# open-book.net
KiCad netlist of a schematic drawn in EAGLE
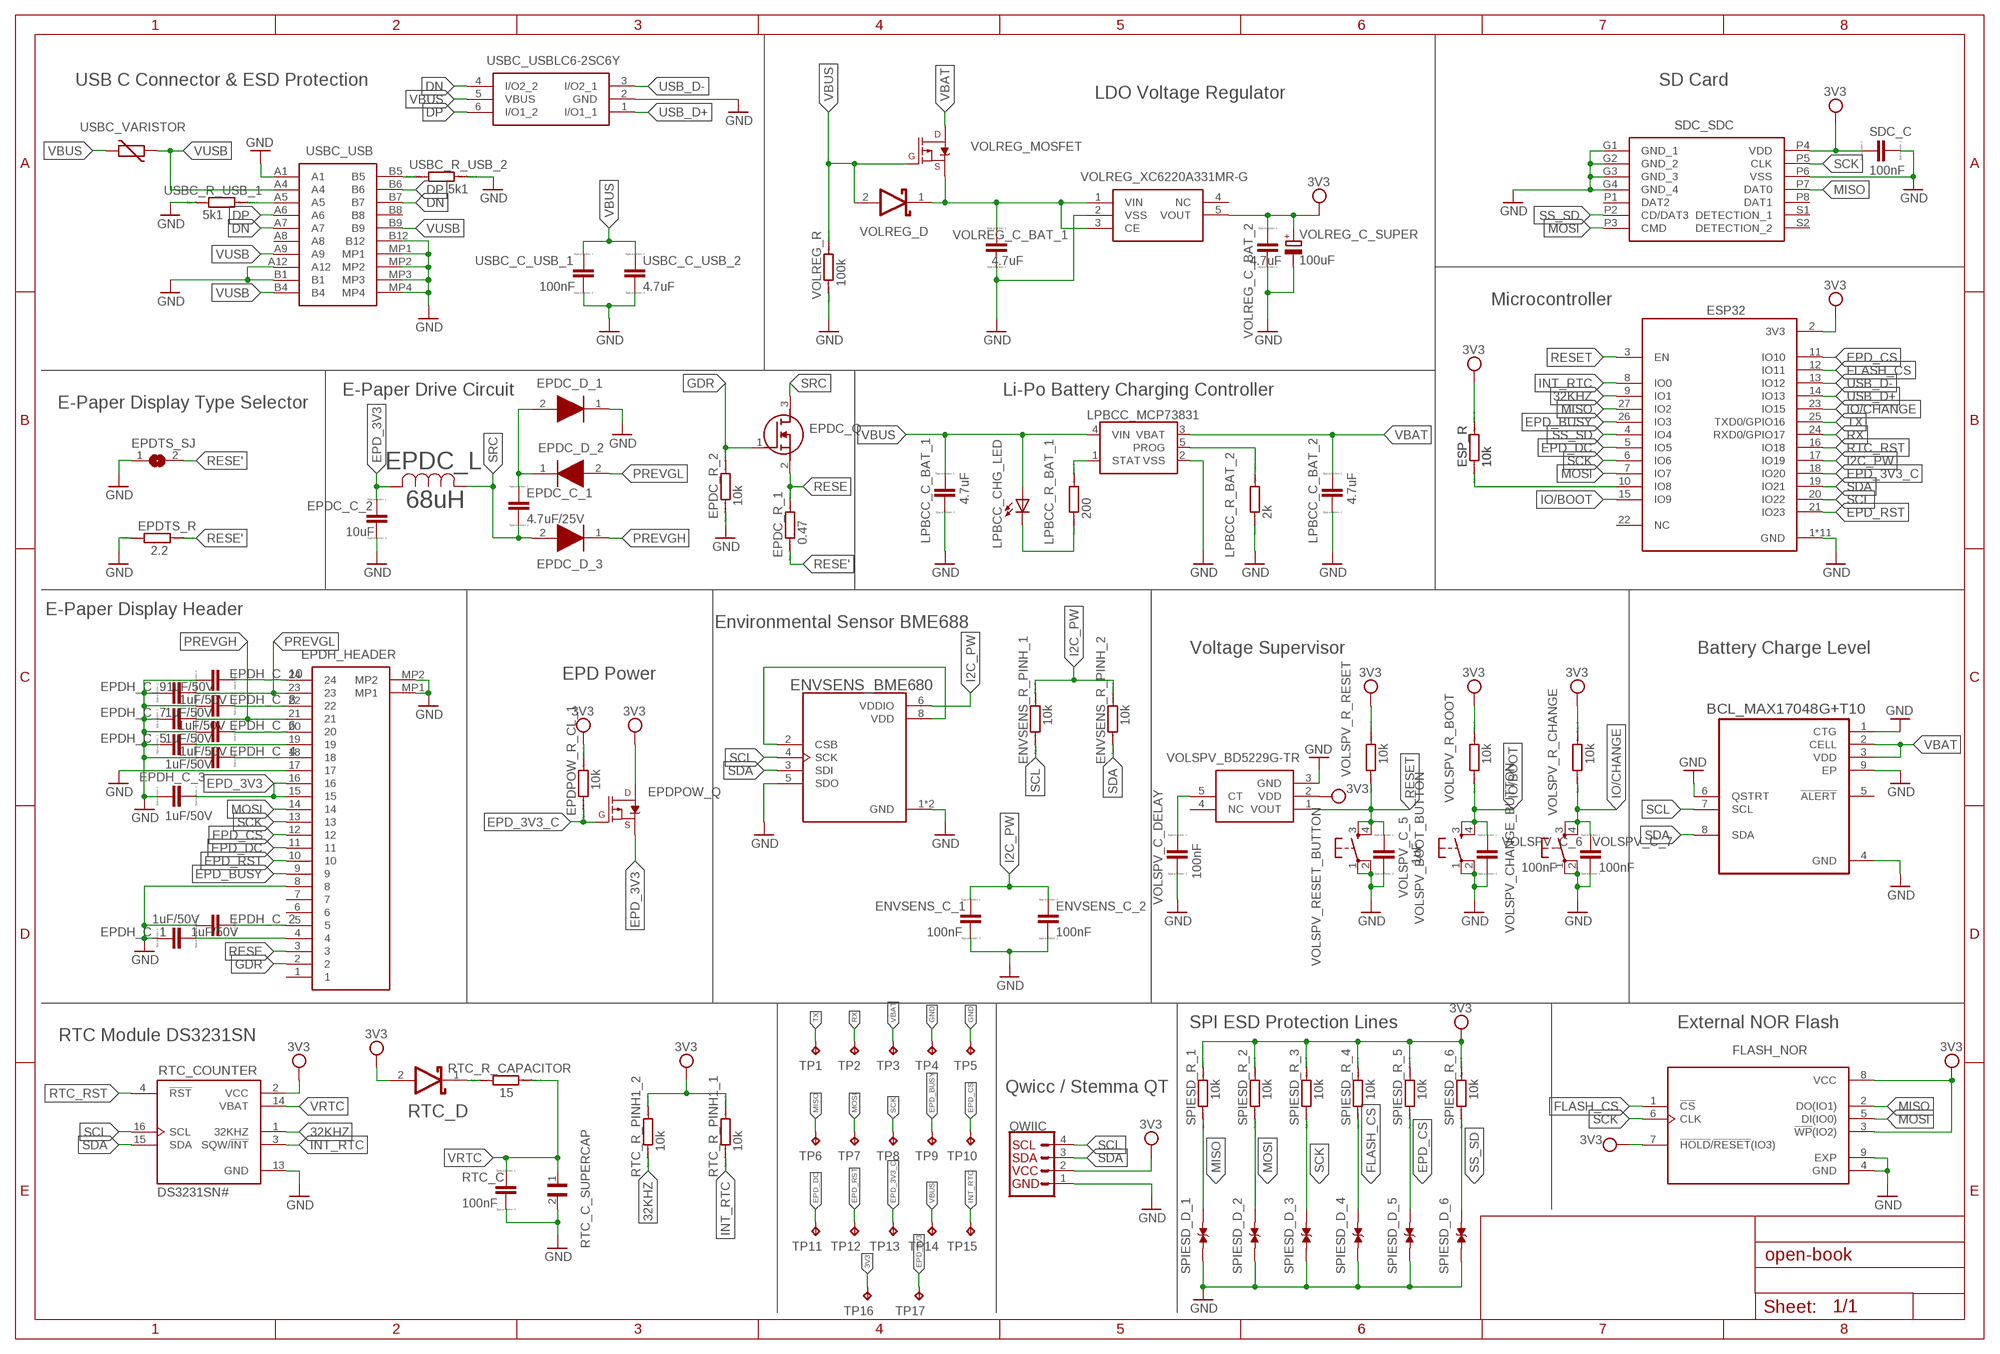
[diagram p0: schematic, sheet 1]

(export (version "E")
  (design (tool "Eeschema 10.0.6"))
  (components
    (comp (ref "BCL_MAX17048G+T10")
      (value "MAX17048G+T10")
      (footprint "eagle-import:SON50P200X200X80-9N")
      (libsource (lib "eagle-import") (part "MAX17048G+T10"))
    )
    (comp (ref "ENVSENS_BME680")
      (value "ESP32_WROVER_BME680_BME680")
      (footprint "eagle-import:ESP32_WROVER_BME680_PSON80P300X300X100-8N")
      (libsource (lib "eagle-import") (part "ESP32_WROVER_BME680_BME680"))
    )
    (comp (ref "ENVSENS_C_1")
      (value "100nF")
      (footprint "eagle-import:EAGLE-LTSPICE_C0402")
      (libsource (lib "eagle-import") (part "EAGLE-LTSPICE_CC0402"))
    )
    (comp (ref "ENVSENS_C_2")
      (value "100nF")
      (footprint "eagle-import:EAGLE-LTSPICE_C0402")
      (libsource (lib "eagle-import") (part "EAGLE-LTSPICE_CC0402"))
    )
    (comp (ref "ENVSENS_R_PINH_1")
      (value "10k")
      (footprint "eagle-import:ESP32_WROVER_EAGLE-LTSPICE_R0402")
      (libsource (lib "eagle-import") (part "ESP32_WROVER_EAGLE-LTSPICE_RR0402"))
    )
    (comp (ref "ENVSENS_R_PINH_2")
      (value "10k")
      (footprint "eagle-import:ESP32_WROVER_EAGLE-LTSPICE_R0402")
      (libsource (lib "eagle-import") (part "ESP32_WROVER_EAGLE-LTSPICE_RR0402"))
    )
    (comp (ref "EPDC_C_1")
      (value "4.7uF/25V")
      (footprint "eagle-import:EAGLE-LTSPICE_C0402")
      (libsource (lib "eagle-import") (part "EAGLE-LTSPICE_CC0402"))
    )
    (comp (ref "EPDC_C_2")
      (value "10uF")
      (footprint "eagle-import:EAGLE-LTSPICE_C0402")
      (libsource (lib "eagle-import") (part "EAGLE-LTSPICE_CC0402"))
    )
    (comp (ref "EPDC_D_1")
      (value "MBR0530")
      (footprint "eagle-import:SOD3716X135N")
      (libsource (lib "eagle-import") (part "MBR0530"))
    )
    (comp (ref "EPDC_D_2")
      (value "MBR0530")
      (footprint "eagle-import:SOD3716X135N")
      (libsource (lib "eagle-import") (part "MBR0530"))
    )
    (comp (ref "EPDC_D_3")
      (value "MBR0530")
      (footprint "eagle-import:SOD3716X135N")
      (libsource (lib "eagle-import") (part "MBR0530"))
    )
    (comp (ref "EPDC_L")
      (value "68uH")
      (footprint "eagle-import:IND_4828-WE-TPC_WRE")
      (libsource (lib "eagle-import") (part "744043680IND_4828-WE-TPC_WRE"))
    )
    (comp (ref "EPDC_Q")
      (value "SI1308EDL-T1-GE3")
      (footprint "eagle-import:SOT65P210X110-3N")
      (libsource (lib "eagle-import") (part "SI1308EDL-T1-GE3"))
    )
    (comp (ref "EPDC_R_1")
      (value "0.47")
      (footprint "eagle-import:ESP32_WROVER_EAGLE-LTSPICE_R0402")
      (libsource (lib "eagle-import") (part "ESP32_WROVER_EAGLE-LTSPICE_RR0402"))
    )
    (comp (ref "EPDC_R_2")
      (value "10k")
      (footprint "eagle-import:ESP32_WROVER_EAGLE-LTSPICE_R0402")
      (libsource (lib "eagle-import") (part "ESP32_WROVER_EAGLE-LTSPICE_RR0402"))
    )
    (comp (ref "EPDH_C_1")
      (value "1uF/50V")
      (footprint "eagle-import:EAGLE-LTSPICE_C0402")
      (libsource (lib "eagle-import") (part "EAGLE-LTSPICE_CC0402"))
    )
    (comp (ref "EPDH_C_2")
      (value "1uF/50V")
      (footprint "eagle-import:EAGLE-LTSPICE_C0402")
      (libsource (lib "eagle-import") (part "EAGLE-LTSPICE_CC0402"))
    )
    (comp (ref "EPDH_C_3")
      (value "1uF/50V")
      (footprint "eagle-import:EAGLE-LTSPICE_C0402")
      (libsource (lib "eagle-import") (part "EAGLE-LTSPICE_CC0402"))
    )
    (comp (ref "EPDH_C_4")
      (value "1uF/50V")
      (footprint "eagle-import:EAGLE-LTSPICE_C0402")
      (libsource (lib "eagle-import") (part "EAGLE-LTSPICE_CC0402"))
    )
    (comp (ref "EPDH_C_5")
      (value "1uF/50V")
      (footprint "eagle-import:EAGLE-LTSPICE_C0402")
      (libsource (lib "eagle-import") (part "EAGLE-LTSPICE_CC0402"))
    )
    (comp (ref "EPDH_C_6")
      (value "1uF/50V")
      (footprint "eagle-import:EAGLE-LTSPICE_C0402")
      (libsource (lib "eagle-import") (part "EAGLE-LTSPICE_CC0402"))
    )
    (comp (ref "EPDH_C_7")
      (value "1uF/50V")
      (footprint "eagle-import:EAGLE-LTSPICE_C0402")
      (libsource (lib "eagle-import") (part "EAGLE-LTSPICE_CC0402"))
    )
    (comp (ref "EPDH_C_8")
      (value "1uF/50V")
      (footprint "eagle-import:EAGLE-LTSPICE_C0402")
      (libsource (lib "eagle-import") (part "EAGLE-LTSPICE_CC0402"))
    )
    (comp (ref "EPDH_C_9")
      (value "1uF/50V")
      (footprint "eagle-import:EAGLE-LTSPICE_C0402")
      (libsource (lib "eagle-import") (part "EAGLE-LTSPICE_CC0402"))
    )
    (comp (ref "EPDH_C_10")
      (value "1uF/50V")
      (footprint "eagle-import:EAGLE-LTSPICE_C0402")
      (libsource (lib "eagle-import") (part "EAGLE-LTSPICE_CC0402"))
    )
    (comp (ref "EPDH_HEADER")
      (value "FH34SRJ-24S-0.5SH_99_")
      (footprint "eagle-import:FH34SRJ24S05SH99")
      (libsource (lib "eagle-import") (part "FH34SRJ-24S-0.5SH_99_"))
    )
    (comp (ref "EPDPOW_Q")
      (value "20V/4.2A/52mΩ/1.4W")
      (footprint "eagle-import:ESP32_WROVER_SPARKFUN-DISCRETESEMI_SOT23-3")
      (libsource (lib "eagle-import") (part "ESP32_WROVER_SPARKFUN-DISCRETESEMI_MOSFET_PCH-DMG2305UX-7"))
    )
    (comp (ref "EPDPOW_R_CL_1")
      (value "10k")
      (footprint "eagle-import:ESP32_WROVER_EAGLE-LTSPICE_R0402")
      (libsource (lib "eagle-import") (part "ESP32_WROVER_EAGLE-LTSPICE_RR0402"))
    )
    (comp (ref "EPDTS_R")
      (value "2.2")
      (footprint "eagle-import:ESP32_WROVER_EAGLE-LTSPICE_R0402")
      (libsource (lib "eagle-import") (part "ESP32_WROVER_EAGLE-LTSPICE_RR0402"))
    )
    (comp (ref "EPDTS_SJ")
      (value "SJ")
      (footprint "eagle-import:SJ")
      (libsource (lib "eagle-import") (part "SJ"))
    )
    (comp (ref "ESP32")
      (value "ESP32-C6-WROOM-1-N8")
      (footprint "eagle-import:XCVR_ESP32-C6-WROOM-1-N8")
      (fields (field (name "MF") "Espressif Systems"))
      (libsource (lib "eagle-import") (part "ESP32-C6-WROOM-1-N8"))
    )
    (comp (ref "ESP_R")
      (value "10k")
      (footprint "eagle-import:ESP32_WROVER_EAGLE-LTSPICE_R0402")
      (libsource (lib "eagle-import") (part "ESP32_WROVER_EAGLE-LTSPICE_RR0402"))
    )
    (comp (ref "FLASH_NOR")
      (value "W25Q512JVEIQ")
      (footprint "eagle-import:SON127P600X800X80-9N")
      (libsource (lib "eagle-import") (part "W25Q512JVEIQ"))
    )
    (comp (ref "LPBCC_CHG_LED")
      (value "ADAFRUIT_LED")
      (footprint "eagle-import:ADAFRUIT_CHIP-LED0603")
      (libsource (lib "eagle-import") (part "ADAFRUIT_LED"))
    )
    (comp (ref "LPBCC_C_BAT_1")
      (value "4.7uF")
      (footprint "eagle-import:EAGLE-LTSPICE_C0402")
      (libsource (lib "eagle-import") (part "EAGLE-LTSPICE_CC0402"))
    )
    (comp (ref "LPBCC_C_BAT_2")
      (value "4.7uF")
      (footprint "eagle-import:EAGLE-LTSPICE_C0402")
      (libsource (lib "eagle-import") (part "EAGLE-LTSPICE_CC0402"))
    )
    (comp (ref "LPBCC_MCP73831")
      (value "ESP32_WROVER_SPARKFUN-IC-POWER_MCP73831")
      (footprint "eagle-import:ESP32_WROVER_SPARKFUN-IC-POWER_SOT23-5")
      (libsource (lib "eagle-import") (part "ESP32_WROVER_SPARKFUN-IC-POWER_MCP73831"))
    )
    (comp (ref "LPBCC_R_BAT_1")
      (value "200")
      (footprint "eagle-import:ESP32_WROVER_EAGLE-LTSPICE_R0402")
      (libsource (lib "eagle-import") (part "ESP32_WROVER_EAGLE-LTSPICE_RR0402"))
    )
    (comp (ref "LPBCC_R_BAT_2")
      (value "2k")
      (footprint "eagle-import:ESP32_WROVER_EAGLE-LTSPICE_R0402")
      (libsource (lib "eagle-import") (part "ESP32_WROVER_EAGLE-LTSPICE_RR0402"))
    )
    (comp (ref "QWIIC")
      (value "QWIIC_RIGHT_ANGLE")
      (footprint "eagle-import:JST04_1MM_RA")
      (libsource (lib "eagle-import") (part "QWIIC_CONNECTORJS-1MM"))
    )
    (comp (ref "RTC_C")
      (value "100nF")
      (footprint "eagle-import:EAGLE-LTSPICE_C0402")
      (libsource (lib "eagle-import") (part "EAGLE-LTSPICE_CC0402"))
    )
    (comp (ref "RTC_COUNTER")
      (value "DS3231SN#")
      (footprint "eagle-import:SOIC127P1032X265-16N")
      (libsource (lib "eagle-import") (part "DS3231SN#"))
    )
    (comp (ref "RTC_C_SUPERCAP")
      (value "CPH3225A")
      (footprint "eagle-import:CAPCP3225X100N")
      (libsource (lib "eagle-import") (part "CPH3225A"))
    )
    (comp (ref "RTC_D")
      (value "ESP32_WROVER_AVX---SD0805S020S1R0_AVX_SD0805S020S1R0_0_0AVX_SD0805S020S1R0_0_0")
      (footprint "eagle-import:ESP32_WROVER_AVX---SD0805S020S1R0_AVX_SD0805S020S1R0_0")
      (libsource (lib "eagle-import") (part "ESP32_WROVER_AVX---SD0805S020S1R0_AVX_SD0805S020S1R0_0_0AVX_SD0805S020S1R0_0_0"))
    )
    (comp (ref "RTC_R_CAPACITOR")
      (value "15")
      (footprint "eagle-import:ESP32_WROVER_EAGLE-LTSPICE_R0402")
      (libsource (lib "eagle-import") (part "ESP32_WROVER_EAGLE-LTSPICE_RR0402"))
    )
    (comp (ref "RTC_R_PINH1_1")
      (value "10k")
      (footprint "eagle-import:ESP32_WROVER_EAGLE-LTSPICE_R0402")
      (libsource (lib "eagle-import") (part "ESP32_WROVER_EAGLE-LTSPICE_RR0402"))
    )
    (comp (ref "RTC_R_PINH1_2")
      (value "10k")
      (footprint "eagle-import:ESP32_WROVER_EAGLE-LTSPICE_R0402")
      (libsource (lib "eagle-import") (part "ESP32_WROVER_EAGLE-LTSPICE_RR0402"))
    )
    (comp (ref "SDC_C")
      (value "100nF")
      (footprint "eagle-import:EAGLE-LTSPICE_C0402")
      (libsource (lib "eagle-import") (part "EAGLE-LTSPICE_CC0402"))
    )
    (comp (ref "SDC_SDC")
      (value "112A-TAAR-R03_ATTEND")
      (footprint "eagle-import:112ATAARR03ATTEND")
      (libsource (lib "eagle-import") (part "112A-TAAR-R03_ATTEND"))
    )
    (comp (ref "SPIESD_D_1")
      (value "PGB1010603MR")
      (footprint "eagle-import:DIOC1608X36N")
      (libsource (lib "eagle-import") (part "PGB1010603MR"))
    )
    (comp (ref "SPIESD_D_2")
      (value "PGB1010603MR")
      (footprint "eagle-import:DIOC1608X36N")
      (libsource (lib "eagle-import") (part "PGB1010603MR"))
    )
    (comp (ref "SPIESD_D_3")
      (value "PGB1010603MR")
      (footprint "eagle-import:DIOC1608X36N")
      (libsource (lib "eagle-import") (part "PGB1010603MR"))
    )
    (comp (ref "SPIESD_D_4")
      (value "PGB1010603MR")
      (footprint "eagle-import:DIOC1608X36N")
      (libsource (lib "eagle-import") (part "PGB1010603MR"))
    )
    (comp (ref "SPIESD_D_5")
      (value "PGB1010603MR")
      (footprint "eagle-import:DIOC1608X36N")
      (libsource (lib "eagle-import") (part "PGB1010603MR"))
    )
    (comp (ref "SPIESD_D_6")
      (value "PGB1010603MR")
      (footprint "eagle-import:DIOC1608X36N")
      (libsource (lib "eagle-import") (part "PGB1010603MR"))
    )
    (comp (ref "SPIESD_R_1")
      (value "10k")
      (footprint "eagle-import:ESP32_WROVER_EAGLE-LTSPICE_R0402")
      (libsource (lib "eagle-import") (part "ESP32_WROVER_EAGLE-LTSPICE_RR0402"))
    )
    (comp (ref "SPIESD_R_2")
      (value "10k")
      (footprint "eagle-import:ESP32_WROVER_EAGLE-LTSPICE_R0402")
      (libsource (lib "eagle-import") (part "ESP32_WROVER_EAGLE-LTSPICE_RR0402"))
    )
    (comp (ref "SPIESD_R_3")
      (value "10k")
      (footprint "eagle-import:ESP32_WROVER_EAGLE-LTSPICE_R0402")
      (libsource (lib "eagle-import") (part "ESP32_WROVER_EAGLE-LTSPICE_RR0402"))
    )
    (comp (ref "SPIESD_R_4")
      (value "10k")
      (footprint "eagle-import:ESP32_WROVER_EAGLE-LTSPICE_R0402")
      (libsource (lib "eagle-import") (part "ESP32_WROVER_EAGLE-LTSPICE_RR0402"))
    )
    (comp (ref "SPIESD_R_5")
      (value "10k")
      (footprint "eagle-import:ESP32_WROVER_EAGLE-LTSPICE_R0402")
      (libsource (lib "eagle-import") (part "ESP32_WROVER_EAGLE-LTSPICE_RR0402"))
    )
    (comp (ref "SPIESD_R_6")
      (value "10k")
      (footprint "eagle-import:ESP32_WROVER_EAGLE-LTSPICE_R0402")
      (libsource (lib "eagle-import") (part "ESP32_WROVER_EAGLE-LTSPICE_RR0402"))
    )
    (comp (ref "TP1")
      (value "TPTP20R")
      (footprint "eagle-import:TP20R")
      (libsource (lib "eagle-import") (part "TPTP20R"))
    )
    (comp (ref "TP2")
      (value "TPTP20R")
      (footprint "eagle-import:TP20R")
      (libsource (lib "eagle-import") (part "TPTP20R"))
    )
    (comp (ref "TP3")
      (value "TPTP20R")
      (footprint "eagle-import:TP20R")
      (libsource (lib "eagle-import") (part "TPTP20R"))
    )
    (comp (ref "TP4")
      (value "TPTP20R")
      (footprint "eagle-import:TP20R")
      (libsource (lib "eagle-import") (part "TPTP20R"))
    )
    (comp (ref "TP5")
      (value "TPTP20R")
      (footprint "eagle-import:TP20R")
      (libsource (lib "eagle-import") (part "TPTP20R"))
    )
    (comp (ref "TP6")
      (value "TPTP20R")
      (footprint "eagle-import:TP20R")
      (libsource (lib "eagle-import") (part "TPTP20R"))
    )
    (comp (ref "TP7")
      (value "TPTP20R")
      (footprint "eagle-import:TP20R")
      (libsource (lib "eagle-import") (part "TPTP20R"))
    )
    (comp (ref "TP8")
      (value "TPTP20R")
      (footprint "eagle-import:TP20R")
      (libsource (lib "eagle-import") (part "TPTP20R"))
    )
    (comp (ref "TP9")
      (value "TPTP20R")
      (footprint "eagle-import:TP20R")
      (libsource (lib "eagle-import") (part "TPTP20R"))
    )
    (comp (ref "TP10")
      (value "TPTP20R")
      (footprint "eagle-import:TP20R")
      (libsource (lib "eagle-import") (part "TPTP20R"))
    )
    (comp (ref "TP11")
      (value "TPTP20R")
      (footprint "eagle-import:TP20R")
      (libsource (lib "eagle-import") (part "TPTP20R"))
    )
    (comp (ref "TP12")
      (value "TPTP20R")
      (footprint "eagle-import:TP20R")
      (libsource (lib "eagle-import") (part "TPTP20R"))
    )
    (comp (ref "TP13")
      (value "TPTP20R")
      (footprint "eagle-import:TP20R")
      (libsource (lib "eagle-import") (part "TPTP20R"))
    )
    (comp (ref "TP14")
      (value "TPTP20R")
      (footprint "eagle-import:TP20R")
      (libsource (lib "eagle-import") (part "TPTP20R"))
    )
    (comp (ref "TP15")
      (value "TPTP20R")
      (footprint "eagle-import:TP20R")
      (libsource (lib "eagle-import") (part "TPTP20R"))
    )
    (comp (ref "TP16")
      (value "TPTP20R")
      (footprint "eagle-import:TP20R")
      (libsource (lib "eagle-import") (part "TPTP20R"))
    )
    (comp (ref "TP17")
      (value "TPTP20R")
      (footprint "eagle-import:TP20R")
      (libsource (lib "eagle-import") (part "TPTP20R"))
    )
    (comp (ref "USBC_C_USB_1")
      (value "100nF")
      (footprint "eagle-import:EAGLE-LTSPICE_C0402")
      (libsource (lib "eagle-import") (part "EAGLE-LTSPICE_CC0402"))
    )
    (comp (ref "USBC_C_USB_2")
      (value "4.7uF")
      (footprint "eagle-import:EAGLE-LTSPICE_C0402")
      (libsource (lib "eagle-import") (part "EAGLE-LTSPICE_CC0402"))
    )
    (comp (ref "USBC_R_USB_1")
      (value "5k1")
      (footprint "eagle-import:ESP32_WROVER_EAGLE-LTSPICE_R0402")
      (libsource (lib "eagle-import") (part "ESP32_WROVER_EAGLE-LTSPICE_RR0402"))
    )
    (comp (ref "USBC_R_USB_2")
      (value "5k1")
      (footprint "eagle-import:ESP32_WROVER_EAGLE-LTSPICE_R0402")
      (libsource (lib "eagle-import") (part "ESP32_WROVER_EAGLE-LTSPICE_RR0402"))
    )
    (comp (ref "USBC_USB")
      (value "SAMACSYS_PARTS_USB4110-GF-A")
      (footprint "eagle-import:SAMACSYS_PARTS_USB4110GFA")
      (libsource (lib "eagle-import") (part "SAMACSYS_PARTS_USB4110-GF-A"))
    )
    (comp (ref "USBC_USBLC6-2SC6Y")
      (value "USBLC6-2SC6Y")
      (footprint "eagle-import:SOT95P280X145-6N")
      (libsource (lib "eagle-import") (part "USBLC6-2SC6Y"))
    )
    (comp (ref "USBC_VARISTOR")
      (value "ESP32C6_VARISTORCN1812")
      (footprint "eagle-import:ESP32C6_VARISTOR_CT_CN1812")
      (libsource (lib "eagle-import") (part "ESP32C6_VARISTORCN1812"))
    )
    (comp (ref "VOLREG_C_BAT_1")
      (value "4.7uF")
      (footprint "eagle-import:EAGLE-LTSPICE_C0402")
      (libsource (lib "eagle-import") (part "EAGLE-LTSPICE_CC0402"))
    )
    (comp (ref "VOLREG_C_BAT_2")
      (value "4.7uF")
      (footprint "eagle-import:EAGLE-LTSPICE_C0402")
      (libsource (lib "eagle-import") (part "EAGLE-LTSPICE_CC0402"))
    )
    (comp (ref "VOLREG_C_SUPER")
      (value "100uF")
      (footprint "eagle-import:RCL_CT3528")
      (libsource (lib "eagle-import") (part "RCL_CPOL-EUCT3528"))
    )
    (comp (ref "VOLREG_D")
      (value "ESP32_WROVER_AVX---SD0805S020S1R0_AVX_SD0805S020S1R0_0_0AVX_SD0805S020S1R0_0_0")
      (footprint "eagle-import:ESP32_WROVER_AVX---SD0805S020S1R0_AVX_SD0805S020S1R0_0")
      (libsource (lib "eagle-import") (part "ESP32_WROVER_AVX---SD0805S020S1R0_AVX_SD0805S020S1R0_0_0AVX_SD0805S020S1R0_0_0"))
    )
    (comp (ref "VOLREG_MOSFET")
      (value "20V/4.2A/52mΩ/1.4W")
      (footprint "eagle-import:ESP32_WROVER_SPARKFUN-DISCRETESEMI_SOT23-3")
      (libsource (lib "eagle-import") (part "ESP32_WROVER_SPARKFUN-DISCRETESEMI_MOSFET_PCH-DMG2305UX-7"))
    )
    (comp (ref "VOLREG_R")
      (value "100k")
      (footprint "eagle-import:ESP32_WROVER_EAGLE-LTSPICE_R0402")
      (libsource (lib "eagle-import") (part "ESP32_WROVER_EAGLE-LTSPICE_RR0402"))
    )
    (comp (ref "VOLREG_XC6220A331MR-G")
      (value "XC6220A331MR-G")
      (footprint "eagle-import:SOT95P280X125-5N")
      (libsource (lib "eagle-import") (part "XC6220A331MR-G"))
    )
    (comp (ref "VOLSPV_BD5229G-TR")
      (value "BD5229G-TR")
      (footprint "eagle-import:SOT95P280X125-5N")
      (libsource (lib "eagle-import") (part "BD5229G-TR"))
    )
    (comp (ref "VOLSPV_BOOT_BUTTON")
      (value "BUTTON_CUSYOMV1")
      (footprint "eagle-import:MYBUTTON")
      (libsource (lib "eagle-import") (part "BUTTON_CUSYOMV1"))
    )
    (comp (ref "VOLSPV_CHANGE_BUTTON")
      (value "BUTTON_CUSYOMV1")
      (footprint "eagle-import:MYBUTTON")
      (libsource (lib "eagle-import") (part "BUTTON_CUSYOMV1"))
    )
    (comp (ref "VOLSPV_C_5")
      (value "1uF")
      (footprint "eagle-import:EAGLE-LTSPICE_C0402")
      (libsource (lib "eagle-import") (part "EAGLE-LTSPICE_CC0402"))
    )
    (comp (ref "VOLSPV_C_6")
      (value "100nF")
      (footprint "eagle-import:EAGLE-LTSPICE_C0402")
      (libsource (lib "eagle-import") (part "EAGLE-LTSPICE_CC0402"))
    )
    (comp (ref "VOLSPV_C_7")
      (value "100nF")
      (footprint "eagle-import:EAGLE-LTSPICE_C0402")
      (libsource (lib "eagle-import") (part "EAGLE-LTSPICE_CC0402"))
    )
    (comp (ref "VOLSPV_C_DELAY")
      (value "100nF")
      (footprint "eagle-import:EAGLE-LTSPICE_C0402")
      (libsource (lib "eagle-import") (part "EAGLE-LTSPICE_CC0402"))
    )
    (comp (ref "VOLSPV_RESET_BUTTON")
      (value "BUTTON_CUSYOMV1")
      (footprint "eagle-import:MYBUTTON")
      (libsource (lib "eagle-import") (part "BUTTON_CUSYOMV1"))
    )
    (comp (ref "VOLSPV_R_BOOT")
      (value "10k")
      (footprint "eagle-import:ESP32_WROVER_EAGLE-LTSPICE_R0402")
      (libsource (lib "eagle-import") (part "ESP32_WROVER_EAGLE-LTSPICE_RR0402"))
    )
    (comp (ref "VOLSPV_R_CHANGE")
      (value "10k")
      (footprint "eagle-import:ESP32_WROVER_EAGLE-LTSPICE_R0402")
      (libsource (lib "eagle-import") (part "ESP32_WROVER_EAGLE-LTSPICE_RR0402"))
    )
    (comp (ref "VOLSPV_R_RESET")
      (value "10k")
      (footprint "eagle-import:ESP32_WROVER_EAGLE-LTSPICE_R0402")
      (libsource (lib "eagle-import") (part "ESP32_WROVER_EAGLE-LTSPICE_RR0402"))
    )
  )
  (nets
    (net (code "1") (name "3V3") (class "Default")
      (node (ref "EPDPOW_Q") (pin "3") (pinfunction "D_3") (pintype "bidirectional"))
      (node (ref "EPDPOW_R_CL_1") (pin "2") (pinfunction "2_2") (pintype "passive"))
      (node (ref "ESP32") (pin "2") (pinfunction "3V3_2") (pintype "power_in"))
      (node (ref "ESP_R") (pin "2") (pinfunction "2_2") (pintype "passive"))
      (node (ref "FLASH_NOR") (pin "3") (pinfunction "~{WP}(IO2)_3") (pintype "bidirectional"))
      (node (ref "FLASH_NOR") (pin "7") (pinfunction "~{HOLD}/~{RESET}(IO3)_7") (pintype "bidirectional"))
      (node (ref "FLASH_NOR") (pin "8") (pinfunction "VCC_8") (pintype "power_in"))
      (node (ref "QWIIC") (pin "2") (pinfunction "2_2") (pintype "power_in"))
      (node (ref "RTC_COUNTER") (pin "2") (pinfunction "VCC_2") (pintype "power_in"))
      (node (ref "RTC_D") (pin "2") (pinfunction "ANODE_2") (pintype "bidirectional"))
      (node (ref "RTC_R_PINH1_1") (pin "2") (pinfunction "2_2") (pintype "passive"))
      (node (ref "RTC_R_PINH1_2") (pin "2") (pinfunction "2_2") (pintype "passive"))
      (node (ref "SDC_C") (pin "1") (pinfunction "1_1") (pintype "passive"))
      (node (ref "SDC_SDC") (pin "P4") (pinfunction "VDD_P4") (pintype "bidirectional"))
      (node (ref "SPIESD_R_1") (pin "2") (pinfunction "2_2") (pintype "passive"))
      (node (ref "SPIESD_R_2") (pin "2") (pinfunction "2_2") (pintype "passive"))
      (node (ref "SPIESD_R_3") (pin "2") (pinfunction "2_2") (pintype "passive"))
      (node (ref "SPIESD_R_4") (pin "2") (pinfunction "2_2") (pintype "passive"))
      (node (ref "SPIESD_R_5") (pin "2") (pinfunction "2_2") (pintype "passive"))
      (node (ref "SPIESD_R_6") (pin "2") (pinfunction "2_2") (pintype "passive"))
      (node (ref "TP16") (pin "TP") (pinfunction "TP_TP") (pintype "input"))
      (node (ref "VOLREG_C_BAT_2") (pin "1") (pinfunction "1_1") (pintype "passive"))
      (node (ref "VOLREG_C_SUPER") (pin "+") (pinfunction "+_+") (pintype "passive"))
      (node (ref "VOLREG_XC6220A331MR-G") (pin "5") (pinfunction "VOUT_5") (pintype "bidirectional"))
      (node (ref "VOLSPV_BD5229G-TR") (pin "2") (pinfunction "VDD_2") (pintype "bidirectional"))
      (node (ref "VOLSPV_R_BOOT") (pin "2") (pinfunction "2_2") (pintype "passive"))
      (node (ref "VOLSPV_R_CHANGE") (pin "2") (pinfunction "2_2") (pintype "passive"))
      (node (ref "VOLSPV_R_RESET") (pin "2") (pinfunction "2_2") (pintype "passive"))
    )
    (net (code "2") (name "32KHZ") (class "Default")
      (node (ref "ESP32") (pin "9") (pinfunction "IO1_9") (pintype "bidirectional"))
      (node (ref "RTC_COUNTER") (pin "1") (pinfunction "32KHZ_1") (pintype "output"))
      (node (ref "RTC_R_PINH1_2") (pin "1") (pinfunction "1_1") (pintype "passive"))
    )
    (net (code "3") (name "DN") (class "Default")
      (node (ref "USBC_USB") (pin "A7") (pinfunction "A7_A7") (pintype "bidirectional"))
      (node (ref "USBC_USB") (pin "B7") (pinfunction "B7_B7") (pintype "bidirectional"))
      (node (ref "USBC_USBLC6-2SC6Y") (pin "4") (pinfunction "I/O2_2_4") (pintype "bidirectional"))
    )
    (net (code "4") (name "DP") (class "Default")
      (node (ref "USBC_USB") (pin "A6") (pinfunction "A6_A6") (pintype "bidirectional"))
      (node (ref "USBC_USB") (pin "B6") (pinfunction "B6_B6") (pintype "bidirectional"))
      (node (ref "USBC_USBLC6-2SC6Y") (pin "6") (pinfunction "I/O1_2_6") (pintype "bidirectional"))
    )
    (net (code "5") (name "EPD_3V3") (class "Default")
      (node (ref "EPDC_C_2") (pin "1") (pinfunction "1_1") (pintype "passive"))
      (node (ref "EPDC_L") (pin "2") (pinfunction "2_2") (pintype "passive"))
      (node (ref "EPDH_C_3") (pin "2") (pinfunction "2_2") (pintype "passive"))
      (node (ref "EPDH_HEADER") (pin "15") (pinfunction "15_15") (pintype "bidirectional"))
      (node (ref "EPDH_HEADER") (pin "16") (pinfunction "16_16") (pintype "bidirectional"))
      (node (ref "EPDPOW_Q") (pin "2") (pinfunction "S_2") (pintype "bidirectional"))
      (node (ref "TP17") (pin "TP") (pinfunction "TP_TP") (pintype "input"))
    )
    (net (code "6") (name "EPD_3V3_C") (class "Default")
      (node (ref "EPDPOW_Q") (pin "1") (pinfunction "G_1") (pintype "bidirectional"))
      (node (ref "EPDPOW_R_CL_1") (pin "1") (pinfunction "1_1") (pintype "passive"))
      (node (ref "ESP32") (pin "18") (pinfunction "IO20_18") (pintype "bidirectional"))
      (node (ref "TP13") (pin "TP") (pinfunction "TP_TP") (pintype "input"))
    )
    (net (code "7") (name "EPD_BUSY") (class "Default")
      (node (ref "EPDH_HEADER") (pin "9") (pinfunction "9_9") (pintype "bidirectional"))
      (node (ref "ESP32") (pin "26") (pinfunction "IO3_26") (pintype "bidirectional"))
      (node (ref "TP9") (pin "TP") (pinfunction "TP_TP") (pintype "input"))
    )
    (net (code "8") (name "EPD_CS") (class "Default")
      (node (ref "EPDH_HEADER") (pin "12") (pinfunction "12_12") (pintype "bidirectional"))
      (node (ref "ESP32") (pin "11") (pinfunction "IO10_11") (pintype "bidirectional"))
      (node (ref "SPIESD_D_5") (pin "2") (pinfunction "2_2") (pintype "passive"))
      (node (ref "SPIESD_R_5") (pin "1") (pinfunction "1_1") (pintype "passive"))
      (node (ref "TP10") (pin "TP") (pinfunction "TP_TP") (pintype "input"))
    )
    (net (code "9") (name "EPD_DC") (class "Default")
      (node (ref "EPDH_HEADER") (pin "11") (pinfunction "11_11") (pintype "bidirectional"))
      (node (ref "ESP32") (pin "5") (pinfunction "IO5_5") (pintype "bidirectional"))
      (node (ref "TP11") (pin "TP") (pinfunction "TP_TP") (pintype "input"))
    )
    (net (code "10") (name "EPD_RST") (class "Default")
      (node (ref "EPDH_HEADER") (pin "10") (pinfunction "10_10") (pintype "bidirectional"))
      (node (ref "ESP32") (pin "21") (pinfunction "IO23_21") (pintype "bidirectional"))
      (node (ref "TP12") (pin "TP") (pinfunction "TP_TP") (pintype "input"))
    )
    (net (code "11") (name "FLASH_CS") (class "Default")
      (node (ref "ESP32") (pin "12") (pinfunction "IO11_12") (pintype "bidirectional"))
      (node (ref "FLASH_NOR") (pin "1") (pinfunction "~{CS}_1") (pintype "input"))
      (node (ref "SPIESD_D_4") (pin "2") (pinfunction "2_2") (pintype "passive"))
      (node (ref "SPIESD_R_4") (pin "1") (pinfunction "1_1") (pintype "passive"))
    )
    (net (code "12") (name "GDR") (class "Default")
      (node (ref "EPDC_Q") (pin "1") (pinfunction "G_1") (pintype "bidirectional"))
      (node (ref "EPDC_R_2") (pin "2") (pinfunction "2_2") (pintype "passive"))
      (node (ref "EPDH_HEADER") (pin "2") (pinfunction "2_2") (pintype "bidirectional"))
    )
    (net (code "13") (name "GND") (class "Default")
      (node (ref "BCL_MAX17048G+T10") (pin "1") (pinfunction "CTG_1") (pintype "power_in"))
      (node (ref "BCL_MAX17048G+T10") (pin "4") (pinfunction "GND_4") (pintype "power_in"))
      (node (ref "BCL_MAX17048G+T10") (pin "6") (pinfunction "QSTRT_6") (pintype "input"))
      (node (ref "BCL_MAX17048G+T10") (pin "9") (pinfunction "EP_9") (pintype "power_in"))
      (node (ref "ENVSENS_BME680") (pin "1") (pinfunction "GND_1") (pintype "power_in"))
      (node (ref "ENVSENS_BME680") (pin "5") (pinfunction "SDO_5") (pintype "bidirectional"))
      (node (ref "ENVSENS_BME680") (pin "7") (pinfunction "GND_7") (pintype "power_in"))
      (node (ref "ENVSENS_C_1") (pin "2") (pinfunction "2_2") (pintype "passive"))
      (node (ref "ENVSENS_C_2") (pin "2") (pinfunction "2_2") (pintype "passive"))
      (node (ref "EPDC_C_2") (pin "2") (pinfunction "2_2") (pintype "passive"))
      (node (ref "EPDC_D_1") (pin "1") (pinfunction "K_1") (pintype "bidirectional"))
      (node (ref "EPDC_R_2") (pin "1") (pinfunction "1_1") (pintype "passive"))
      (node (ref "EPDH_C_1") (pin "1") (pinfunction "1_1") (pintype "passive"))
      (node (ref "EPDH_C_10") (pin "1") (pinfunction "1_1") (pintype "passive"))
      (node (ref "EPDH_C_2") (pin "1") (pinfunction "1_1") (pintype "passive"))
      (node (ref "EPDH_C_3") (pin "1") (pinfunction "1_1") (pintype "passive"))
      (node (ref "EPDH_C_4") (pin "1") (pinfunction "1_1") (pintype "passive"))
      (node (ref "EPDH_C_5") (pin "1") (pinfunction "1_1") (pintype "passive"))
      (node (ref "EPDH_C_6") (pin "1") (pinfunction "1_1") (pintype "passive"))
      (node (ref "EPDH_C_7") (pin "1") (pinfunction "1_1") (pintype "passive"))
      (node (ref "EPDH_C_8") (pin "1") (pinfunction "1_1") (pintype "passive"))
      (node (ref "EPDH_C_9") (pin "1") (pinfunction "1_1") (pintype "passive"))
      (node (ref "EPDH_HEADER") (pin "17") (pinfunction "17_17") (pintype "bidirectional"))
      (node (ref "EPDH_HEADER") (pin "8") (pinfunction "8_8") (pintype "bidirectional"))
      (node (ref "EPDH_HEADER") (pin "MP1") (pinfunction "MP1_MP1") (pintype "bidirectional"))
      (node (ref "EPDH_HEADER") (pin "MP2") (pinfunction "MP2_MP2") (pintype "bidirectional"))
      (node (ref "EPDTS_R") (pin "1") (pinfunction "1_1") (pintype "passive"))
      (node (ref "EPDTS_SJ") (pin "1") (pinfunction "1_1") (pintype "passive"))
      (node (ref "ESP32") (pin "1") (pinfunction "GND_1") (pintype "power_in"))
      (node (ref "ESP32") (pin "28") (pinfunction "GND_28") (pintype "power_in"))
      (node (ref "ESP32") (pin "29_1") (pinfunction "GND_29_1") (pintype "power_in"))
      (node (ref "ESP32") (pin "29_2") (pinfunction "GND_29_2") (pintype "power_in"))
      (node (ref "ESP32") (pin "29_3") (pinfunction "GND_29_3") (pintype "power_in"))
      (node (ref "ESP32") (pin "29_4") (pinfunction "GND_29_4") (pintype "power_in"))
      (node (ref "ESP32") (pin "29_5") (pinfunction "GND_29_5") (pintype "power_in"))
      (node (ref "ESP32") (pin "29_6") (pinfunction "GND_29_6") (pintype "power_in"))
      (node (ref "ESP32") (pin "29_7") (pinfunction "GND_29_7") (pintype "power_in"))
      (node (ref "ESP32") (pin "29_8") (pinfunction "GND_29_8") (pintype "power_in"))
      (node (ref "ESP32") (pin "29_9") (pinfunction "GND_29_9") (pintype "power_in"))
      (node (ref "FLASH_NOR") (pin "4") (pinfunction "GND_4") (pintype "power_in"))
      (node (ref "FLASH_NOR") (pin "9") (pinfunction "EXP_9") (pintype "passive"))
      (node (ref "LPBCC_C_BAT_1") (pin "2") (pinfunction "2_2") (pintype "passive"))
      (node (ref "LPBCC_C_BAT_2") (pin "2") (pinfunction "2_2") (pintype "passive"))
      (node (ref "LPBCC_MCP73831") (pin "2") (pinfunction "VSS_2") (pintype "power_in"))
      (node (ref "LPBCC_R_BAT_2") (pin "1") (pinfunction "1_1") (pintype "passive"))
      (node (ref "QWIIC") (pin "1") (pinfunction "1_1") (pintype "power_in"))
      (node (ref "RTC_C") (pin "2") (pinfunction "2_2") (pintype "passive"))
      (node (ref "RTC_COUNTER") (pin "13") (pinfunction "GND_13") (pintype "power_in"))
      (node (ref "RTC_C_SUPERCAP") (pin "2") (pinfunction "2_2") (pintype "passive"))
      (node (ref "SDC_C") (pin "2") (pinfunction "2_2") (pintype "passive"))
      (node (ref "SDC_SDC") (pin "G1") (pinfunction "GND_1_G1") (pintype "bidirectional"))
      (node (ref "SDC_SDC") (pin "G2") (pinfunction "GND_2_G2") (pintype "bidirectional"))
      (node (ref "SDC_SDC") (pin "G3") (pinfunction "GND_3_G3") (pintype "bidirectional"))
      (node (ref "SDC_SDC") (pin "G4") (pinfunction "GND_4_G4") (pintype "bidirectional"))
      (node (ref "SDC_SDC") (pin "P6") (pinfunction "VSS_P6") (pintype "bidirectional"))
      (node (ref "SPIESD_D_1") (pin "1") (pinfunction "1_1") (pintype "passive"))
      (node (ref "SPIESD_D_2") (pin "1") (pinfunction "1_1") (pintype "passive"))
      (node (ref "SPIESD_D_3") (pin "1") (pinfunction "1_1") (pintype "passive"))
      (node (ref "SPIESD_D_4") (pin "1") (pinfunction "1_1") (pintype "passive"))
      (node (ref "SPIESD_D_5") (pin "1") (pinfunction "1_1") (pintype "passive"))
      (node (ref "SPIESD_D_6") (pin "1") (pinfunction "1_1") (pintype "passive"))
      (node (ref "TP4") (pin "TP") (pinfunction "TP_TP") (pintype "input"))
      (node (ref "TP5") (pin "TP") (pinfunction "TP_TP") (pintype "input"))
      (node (ref "USBC_C_USB_1") (pin "2") (pinfunction "2_2") (pintype "passive"))
      (node (ref "USBC_C_USB_2") (pin "2") (pinfunction "2_2") (pintype "passive"))
      (node (ref "USBC_R_USB_1") (pin "1") (pinfunction "1_1") (pintype "passive"))
      (node (ref "USBC_R_USB_2") (pin "2") (pinfunction "2_2") (pintype "passive"))
      (node (ref "USBC_USB") (pin "A1") (pinfunction "A1_A1") (pintype "bidirectional"))
      (node (ref "USBC_USB") (pin "A12") (pinfunction "A12_A12") (pintype "bidirectional"))
      (node (ref "USBC_USB") (pin "B1") (pinfunction "B1_B1") (pintype "bidirectional"))
      (node (ref "USBC_USB") (pin "B12") (pinfunction "B12_B12") (pintype "bidirectional"))
      (node (ref "USBC_USB") (pin "MP1") (pinfunction "MP1_MP1") (pintype "bidirectional"))
      (node (ref "USBC_USB") (pin "MP2") (pinfunction "MP2_MP2") (pintype "bidirectional"))
      (node (ref "USBC_USB") (pin "MP3") (pinfunction "MP3_MP3") (pintype "bidirectional"))
      (node (ref "USBC_USB") (pin "MP4") (pinfunction "MP4_MP4") (pintype "bidirectional"))
      (node (ref "USBC_USBLC6-2SC6Y") (pin "2") (pinfunction "GND_2") (pintype "bidirectional"))
      (node (ref "VOLREG_C_BAT_1") (pin "2") (pinfunction "2_2") (pintype "passive"))
      (node (ref "VOLREG_C_BAT_2") (pin "2") (pinfunction "2_2") (pintype "passive"))
      (node (ref "VOLREG_C_SUPER") (pin "-") (pinfunction "-_-") (pintype "passive"))
      (node (ref "VOLREG_R") (pin "1") (pinfunction "1_1") (pintype "passive"))
      (node (ref "VOLREG_XC6220A331MR-G") (pin "2") (pinfunction "VSS_2") (pintype "bidirectional"))
      (node (ref "VOLSPV_BD5229G-TR") (pin "3") (pinfunction "GND_3") (pintype "bidirectional"))
      (node (ref "VOLSPV_BOOT_BUTTON") (pin "1") (pinfunction "1_1") (pintype "passive"))
      (node (ref "VOLSPV_BOOT_BUTTON") (pin "2") (pinfunction "2_2") (pintype "passive"))
      (node (ref "VOLSPV_CHANGE_BUTTON") (pin "1") (pinfunction "1_1") (pintype "passive"))
      (node (ref "VOLSPV_CHANGE_BUTTON") (pin "2") (pinfunction "2_2") (pintype "passive"))
      (node (ref "VOLSPV_C_5") (pin "2") (pinfunction "2_2") (pintype "passive"))
      (node (ref "VOLSPV_C_6") (pin "2") (pinfunction "2_2") (pintype "passive"))
      (node (ref "VOLSPV_C_7") (pin "2") (pinfunction "2_2") (pintype "passive"))
      (node (ref "VOLSPV_C_DELAY") (pin "2") (pinfunction "2_2") (pintype "passive"))
      (node (ref "VOLSPV_RESET_BUTTON") (pin "1") (pinfunction "1_1") (pintype "passive"))
      (node (ref "VOLSPV_RESET_BUTTON") (pin "2") (pinfunction "2_2") (pintype "passive"))
    )
    (net (code "14") (name "I2C_PW") (class "Default")
      (node (ref "ENVSENS_BME680") (pin "6") (pinfunction "VDDIO_6") (pintype "power_in"))
      (node (ref "ENVSENS_C_1") (pin "1") (pinfunction "1_1") (pintype "passive"))
      (node (ref "ENVSENS_C_2") (pin "1") (pinfunction "1_1") (pintype "passive"))
      (node (ref "ENVSENS_R_PINH_1") (pin "2") (pinfunction "2_2") (pintype "passive"))
      (node (ref "ENVSENS_R_PINH_2") (pin "2") (pinfunction "2_2") (pintype "passive"))
      (node (ref "ESP32") (pin "17") (pinfunction "IO19_17") (pintype "bidirectional"))
    )
    (net (code "15") (name "INT_RTC") (class "Default")
      (node (ref "ESP32") (pin "8") (pinfunction "IO0_8") (pintype "bidirectional"))
      (node (ref "RTC_COUNTER") (pin "3") (pinfunction "SQW/~{INT}_3") (pintype "output"))
      (node (ref "RTC_R_PINH1_1") (pin "1") (pinfunction "1_1") (pintype "passive"))
      (node (ref "TP15") (pin "TP") (pinfunction "TP_TP") (pintype "input"))
    )
    (net (code "16") (name "IO{slash}BOOT") (class "Default")
      (node (ref "ESP32") (pin "15") (pinfunction "IO9_15") (pintype "bidirectional"))
      (node (ref "VOLSPV_BOOT_BUTTON") (pin "3") (pinfunction "3_3") (pintype "passive"))
      (node (ref "VOLSPV_BOOT_BUTTON") (pin "4") (pinfunction "4_4") (pintype "passive"))
      (node (ref "VOLSPV_C_6") (pin "1") (pinfunction "1_1") (pintype "passive"))
      (node (ref "VOLSPV_R_BOOT") (pin "1") (pinfunction "1_1") (pintype "passive"))
    )
    (net (code "17") (name "IO{slash}CHANGE") (class "Default")
      (node (ref "ESP32") (pin "23") (pinfunction "IO15_23") (pintype "bidirectional"))
      (node (ref "VOLSPV_CHANGE_BUTTON") (pin "3") (pinfunction "3_3") (pintype "passive"))
      (node (ref "VOLSPV_CHANGE_BUTTON") (pin "4") (pinfunction "4_4") (pintype "passive"))
      (node (ref "VOLSPV_C_7") (pin "1") (pinfunction "1_1") (pintype "passive"))
      (node (ref "VOLSPV_R_CHANGE") (pin "1") (pinfunction "1_1") (pintype "passive"))
    )
    (net (code "18") (name "MISO") (class "Default")
      (node (ref "ESP32") (pin "27") (pinfunction "IO2_27") (pintype "bidirectional"))
      (node (ref "FLASH_NOR") (pin "2") (pinfunction "DO(IO1)_2") (pintype "bidirectional"))
      (node (ref "SDC_SDC") (pin "P7") (pinfunction "DAT0_P7") (pintype "bidirectional"))
      (node (ref "SPIESD_D_1") (pin "2") (pinfunction "2_2") (pintype "passive"))
      (node (ref "SPIESD_R_1") (pin "1") (pinfunction "1_1") (pintype "passive"))
      (node (ref "TP6") (pin "TP") (pinfunction "TP_TP") (pintype "input"))
    )
    (net (code "19") (name "MOSI") (class "Default")
      (node (ref "EPDH_HEADER") (pin "14") (pinfunction "14_14") (pintype "bidirectional"))
      (node (ref "ESP32") (pin "7") (pinfunction "IO7_7") (pintype "bidirectional"))
      (node (ref "FLASH_NOR") (pin "5") (pinfunction "DI(IO0)_5") (pintype "bidirectional"))
      (node (ref "SDC_SDC") (pin "P3") (pinfunction "CMD_P3") (pintype "bidirectional"))
      (node (ref "SPIESD_D_2") (pin "2") (pinfunction "2_2") (pintype "passive"))
      (node (ref "SPIESD_R_2") (pin "1") (pinfunction "1_1") (pintype "passive"))
      (node (ref "TP7") (pin "TP") (pinfunction "TP_TP") (pintype "input"))
    )
    (net (code "20") (name "Net-(ENVSENS_BME680-CSB)") (class "Default")
      (node (ref "ENVSENS_BME680") (pin "2") (pinfunction "CSB_2") (pintype "input"))
      (node (ref "ENVSENS_BME680") (pin "8") (pinfunction "VDD_8") (pintype "power_in"))
    )
    (net (code "21") (name "Net-(EPDC_D_1-A)") (class "Default")
      (node (ref "EPDC_C_1") (pin "1") (pinfunction "1_1") (pintype "passive"))
      (node (ref "EPDC_D_1") (pin "2") (pinfunction "A_2") (pintype "bidirectional"))
      (node (ref "EPDC_D_2") (pin "1") (pinfunction "K_1") (pintype "bidirectional"))
    )
    (net (code "22") (name "Net-(EPDH_C_1-Pad2)") (class "Default")
      (node (ref "EPDH_C_1") (pin "2") (pinfunction "2_2") (pintype "passive"))
      (node (ref "EPDH_HEADER") (pin "4") (pinfunction "4_4") (pintype "bidirectional"))
    )
    (net (code "23") (name "Net-(EPDH_C_2-Pad2)") (class "Default")
      (node (ref "EPDH_C_2") (pin "2") (pinfunction "2_2") (pintype "passive"))
      (node (ref "EPDH_HEADER") (pin "5") (pinfunction "5_5") (pintype "bidirectional"))
    )
    (net (code "24") (name "Net-(EPDH_C_4-Pad2)") (class "Default")
      (node (ref "EPDH_C_4") (pin "2") (pinfunction "2_2") (pintype "passive"))
      (node (ref "EPDH_HEADER") (pin "18") (pinfunction "18_18") (pintype "bidirectional"))
    )
    (net (code "25") (name "Net-(EPDH_C_5-Pad2)") (class "Default")
      (node (ref "EPDH_C_5") (pin "2") (pinfunction "2_2") (pintype "passive"))
      (node (ref "EPDH_HEADER") (pin "19") (pinfunction "19_19") (pintype "bidirectional"))
    )
    (net (code "26") (name "Net-(EPDH_C_6-Pad2)") (class "Default")
      (node (ref "EPDH_C_6") (pin "2") (pinfunction "2_2") (pintype "passive"))
      (node (ref "EPDH_HEADER") (pin "20") (pinfunction "20_20") (pintype "bidirectional"))
    )
    (net (code "27") (name "Net-(EPDH_C_8-Pad2)") (class "Default")
      (node (ref "EPDH_C_8") (pin "2") (pinfunction "2_2") (pintype "passive"))
      (node (ref "EPDH_HEADER") (pin "22") (pinfunction "22_22") (pintype "bidirectional"))
    )
    (net (code "28") (name "Net-(EPDH_C_10-Pad2)") (class "Default")
      (node (ref "EPDH_C_10") (pin "2") (pinfunction "2_2") (pintype "passive"))
      (node (ref "EPDH_HEADER") (pin "24") (pinfunction "24_24") (pintype "bidirectional"))
    )
    (net (code "29") (name "Net-(ESP32-IO8)") (class "Default")
      (node (ref "ESP32") (pin "10") (pinfunction "IO8_10") (pintype "bidirectional"))
      (node (ref "ESP_R") (pin "1") (pinfunction "1_1") (pintype "passive"))
    )
    (net (code "30") (name "Net-(LPBCC_CHG_LED-PadC)") (class "Default")
      (node (ref "LPBCC_CHG_LED") (pin "C") (pinfunction "C_C") (pintype "passive"))
      (node (ref "LPBCC_R_BAT_1") (pin "1") (pinfunction "1_1") (pintype "passive"))
    )
    (net (code "31") (name "Net-(LPBCC_MCP73831-PROG)") (class "Default")
      (node (ref "LPBCC_MCP73831") (pin "5") (pinfunction "PROG_5") (pintype "input"))
      (node (ref "LPBCC_R_BAT_2") (pin "2") (pinfunction "2_2") (pintype "passive"))
    )
    (net (code "32") (name "Net-(LPBCC_MCP73831-STAT)") (class "Default")
      (node (ref "LPBCC_MCP73831") (pin "1") (pinfunction "STAT_1") (pintype "output"))
      (node (ref "LPBCC_R_BAT_1") (pin "2") (pinfunction "2_2") (pintype "passive"))
    )
    (net (code "33") (name "Net-(RTC_D-CATHODE)") (class "Default")
      (node (ref "RTC_D") (pin "1") (pinfunction "CATHODE_1") (pintype "bidirectional"))
      (node (ref "RTC_R_CAPACITOR") (pin "1") (pinfunction "1_1") (pintype "passive"))
    )
    (net (code "34") (name "Net-(USBC_R_USB_1-Pad2)") (class "Default")
      (node (ref "USBC_R_USB_1") (pin "2") (pinfunction "2_2") (pintype "passive"))
      (node (ref "USBC_USB") (pin "A5") (pinfunction "A5_A5") (pintype "bidirectional"))
    )
    (net (code "35") (name "Net-(USBC_R_USB_2-Pad1)") (class "Default")
      (node (ref "USBC_R_USB_2") (pin "1") (pinfunction "1_1") (pintype "passive"))
      (node (ref "USBC_USB") (pin "B5") (pinfunction "B5_B5") (pintype "bidirectional"))
    )
    (net (code "36") (name "Net-(VOLREG_D-CATHODE)") (class "Default")
      (node (ref "VOLREG_C_BAT_1") (pin "1") (pinfunction "1_1") (pintype "passive"))
      (node (ref "VOLREG_D") (pin "1") (pinfunction "CATHODE_1") (pintype "bidirectional"))
      (node (ref "VOLREG_MOSFET") (pin "2") (pinfunction "S_2") (pintype "bidirectional"))
      (node (ref "VOLREG_XC6220A331MR-G") (pin "1") (pinfunction "VIN_1") (pintype "bidirectional"))
      (node (ref "VOLREG_XC6220A331MR-G") (pin "3") (pinfunction "CE_3") (pintype "bidirectional"))
    )
    (net (code "37") (name "Net-(VOLSPV_BD5229G-TR-CT)") (class "Default")
      (node (ref "VOLSPV_BD5229G-TR") (pin "5") (pinfunction "CT_5") (pintype "bidirectional"))
      (node (ref "VOLSPV_C_DELAY") (pin "1") (pinfunction "1_1") (pintype "passive"))
    )
    (net (code "38") (name "PREVGH") (class "Default")
      (node (ref "EPDC_D_3") (pin "1") (pinfunction "K_1") (pintype "bidirectional"))
      (node (ref "EPDH_C_7") (pin "2") (pinfunction "2_2") (pintype "passive"))
      (node (ref "EPDH_HEADER") (pin "21") (pinfunction "21_21") (pintype "bidirectional"))
    )
    (net (code "39") (name "PREVGL") (class "Default")
      (node (ref "EPDC_D_2") (pin "2") (pinfunction "A_2") (pintype "bidirectional"))
      (node (ref "EPDH_C_9") (pin "2") (pinfunction "2_2") (pintype "passive"))
      (node (ref "EPDH_HEADER") (pin "23") (pinfunction "23_23") (pintype "bidirectional"))
    )
    (net (code "40") (name "RESE") (class "Default")
      (node (ref "EPDC_Q") (pin "2") (pinfunction "S_2") (pintype "bidirectional"))
      (node (ref "EPDC_R_1") (pin "2") (pinfunction "2_2") (pintype "passive"))
      (node (ref "EPDH_HEADER") (pin "3") (pinfunction "3_3") (pintype "bidirectional"))
    )
    (net (code "41") (name "RESE'") (class "Default")
      (node (ref "EPDC_R_1") (pin "1") (pinfunction "1_1") (pintype "passive"))
      (node (ref "EPDTS_R") (pin "2") (pinfunction "2_2") (pintype "passive"))
      (node (ref "EPDTS_SJ") (pin "2") (pinfunction "2_2") (pintype "passive"))
    )
    (net (code "42") (name "RESET") (class "Default")
      (node (ref "ESP32") (pin "3") (pinfunction "EN_3") (pintype "input"))
      (node (ref "VOLSPV_BD5229G-TR") (pin "1") (pinfunction "VOUT_1") (pintype "bidirectional"))
      (node (ref "VOLSPV_C_5") (pin "1") (pinfunction "1_1") (pintype "passive"))
      (node (ref "VOLSPV_RESET_BUTTON") (pin "3") (pinfunction "3_3") (pintype "passive"))
      (node (ref "VOLSPV_RESET_BUTTON") (pin "4") (pinfunction "4_4") (pintype "passive"))
      (node (ref "VOLSPV_R_RESET") (pin "1") (pinfunction "1_1") (pintype "passive"))
    )
    (net (code "43") (name "RTC_RST") (class "Default")
      (node (ref "ESP32") (pin "16") (pinfunction "IO18_16") (pintype "bidirectional"))
      (node (ref "RTC_COUNTER") (pin "4") (pinfunction "~{RST}_4") (pintype "input"))
    )
    (net (code "44") (name "RX") (class "Default")
      (node (ref "ESP32") (pin "24") (pinfunction "RXD0/GPIO17_24") (pintype "bidirectional"))
      (node (ref "TP2") (pin "TP") (pinfunction "TP_TP") (pintype "input"))
    )
    (net (code "45") (name "SCK") (class "Default")
      (node (ref "EPDH_HEADER") (pin "13") (pinfunction "13_13") (pintype "bidirectional"))
      (node (ref "ESP32") (pin "6") (pinfunction "IO6_6") (pintype "bidirectional"))
      (node (ref "FLASH_NOR") (pin "6") (pinfunction "CLK_6") (pintype "input"))
      (node (ref "SDC_SDC") (pin "P5") (pinfunction "CLK_P5") (pintype "bidirectional"))
      (node (ref "SPIESD_D_3") (pin "2") (pinfunction "2_2") (pintype "passive"))
      (node (ref "SPIESD_R_3") (pin "1") (pinfunction "1_1") (pintype "passive"))
      (node (ref "TP8") (pin "TP") (pinfunction "TP_TP") (pintype "input"))
    )
    (net (code "46") (name "SCL") (class "Default")
      (node (ref "BCL_MAX17048G+T10") (pin "7") (pinfunction "SCL_7") (pintype "input"))
      (node (ref "ENVSENS_BME680") (pin "4") (pinfunction "SCK_4") (pintype "input"))
      (node (ref "ENVSENS_R_PINH_1") (pin "1") (pinfunction "1_1") (pintype "passive"))
      (node (ref "ESP32") (pin "20") (pinfunction "IO22_20") (pintype "bidirectional"))
      (node (ref "QWIIC") (pin "4") (pinfunction "4_4") (pintype "passive"))
      (node (ref "RTC_COUNTER") (pin "16") (pinfunction "SCL_16") (pintype "input"))
    )
    (net (code "47") (name "SDA") (class "Default")
      (node (ref "BCL_MAX17048G+T10") (pin "8") (pinfunction "SDA_8") (pintype "bidirectional"))
      (node (ref "ENVSENS_BME680") (pin "3") (pinfunction "SDI_3") (pintype "bidirectional"))
      (node (ref "ENVSENS_R_PINH_2") (pin "1") (pinfunction "1_1") (pintype "passive"))
      (node (ref "ESP32") (pin "19") (pinfunction "IO21_19") (pintype "bidirectional"))
      (node (ref "QWIIC") (pin "3") (pinfunction "3_3") (pintype "passive"))
      (node (ref "RTC_COUNTER") (pin "15") (pinfunction "SDA_15") (pintype "bidirectional"))
    )
    (net (code "48") (name "SRC") (class "Default")
      (node (ref "EPDC_C_1") (pin "2") (pinfunction "2_2") (pintype "passive"))
      (node (ref "EPDC_D_3") (pin "2") (pinfunction "A_2") (pintype "bidirectional"))
      (node (ref "EPDC_L") (pin "1") (pinfunction "1_1") (pintype "passive"))
      (node (ref "EPDC_Q") (pin "3") (pinfunction "D_3") (pintype "bidirectional"))
    )
    (net (code "49") (name "SS_SD") (class "Default")
      (node (ref "ESP32") (pin "4") (pinfunction "IO4_4") (pintype "bidirectional"))
      (node (ref "SDC_SDC") (pin "P2") (pinfunction "CD/DAT3_P2") (pintype "bidirectional"))
      (node (ref "SPIESD_D_6") (pin "2") (pinfunction "2_2") (pintype "passive"))
      (node (ref "SPIESD_R_6") (pin "1") (pinfunction "1_1") (pintype "passive"))
    )
    (net (code "50") (name "TX") (class "Default")
      (node (ref "ESP32") (pin "25") (pinfunction "TXD0/GPIO16_25") (pintype "bidirectional"))
      (node (ref "TP1") (pin "TP") (pinfunction "TP_TP") (pintype "input"))
    )
    (net (code "51") (name "USB_D+") (class "Default")
      (node (ref "ESP32") (pin "14") (pinfunction "IO13_14") (pintype "bidirectional"))
      (node (ref "USBC_USBLC6-2SC6Y") (pin "1") (pinfunction "I/O1_1_1") (pintype "bidirectional"))
    )
    (net (code "52") (name "USB_D-") (class "Default")
      (node (ref "ESP32") (pin "13") (pinfunction "IO12_13") (pintype "bidirectional"))
      (node (ref "USBC_USBLC6-2SC6Y") (pin "3") (pinfunction "I/O2_1_3") (pintype "bidirectional"))
    )
    (net (code "53") (name "VBAT") (class "Default")
      (node (ref "BCL_MAX17048G+T10") (pin "2") (pinfunction "CELL_2") (pintype "power_in"))
      (node (ref "BCL_MAX17048G+T10") (pin "3") (pinfunction "VDD_3") (pintype "power_in"))
      (node (ref "LPBCC_C_BAT_2") (pin "1") (pinfunction "1_1") (pintype "passive"))
      (node (ref "LPBCC_MCP73831") (pin "3") (pinfunction "VBAT_3") (pintype "power_in"))
      (node (ref "TP3") (pin "TP") (pinfunction "TP_TP") (pintype "input"))
      (node (ref "VOLREG_MOSFET") (pin "3") (pinfunction "D_3") (pintype "bidirectional"))
    )
    (net (code "54") (name "VBUS") (class "Default")
      (node (ref "LPBCC_CHG_LED") (pin "A") (pinfunction "A_A") (pintype "passive"))
      (node (ref "LPBCC_C_BAT_1") (pin "1") (pinfunction "1_1") (pintype "passive"))
      (node (ref "LPBCC_MCP73831") (pin "4") (pinfunction "VIN_4") (pintype "power_in"))
      (node (ref "TP14") (pin "TP") (pinfunction "TP_TP") (pintype "input"))
      (node (ref "USBC_C_USB_1") (pin "1") (pinfunction "1_1") (pintype "passive"))
      (node (ref "USBC_C_USB_2") (pin "1") (pinfunction "1_1") (pintype "passive"))
      (node (ref "USBC_USBLC6-2SC6Y") (pin "5") (pinfunction "VBUS_5") (pintype "bidirectional"))
      (node (ref "USBC_VARISTOR") (pin "2") (pinfunction "2_2") (pintype "passive"))
      (node (ref "VOLREG_D") (pin "2") (pinfunction "ANODE_2") (pintype "bidirectional"))
      (node (ref "VOLREG_MOSFET") (pin "1") (pinfunction "G_1") (pintype "bidirectional"))
      (node (ref "VOLREG_R") (pin "2") (pinfunction "2_2") (pintype "passive"))
    )
    (net (code "55") (name "VRTC") (class "Default")
      (node (ref "RTC_C") (pin "1") (pinfunction "1_1") (pintype "passive"))
      (node (ref "RTC_COUNTER") (pin "14") (pinfunction "VBAT_14") (pintype "power_in"))
      (node (ref "RTC_C_SUPERCAP") (pin "1") (pinfunction "1_1") (pintype "passive"))
      (node (ref "RTC_R_CAPACITOR") (pin "2") (pinfunction "2_2") (pintype "passive"))
    )
    (net (code "56") (name "VUSB") (class "Default")
      (node (ref "USBC_USB") (pin "A4") (pinfunction "A4_A4") (pintype "bidirectional"))
      (node (ref "USBC_USB") (pin "A9") (pinfunction "A9_A9") (pintype "bidirectional"))
      (node (ref "USBC_USB") (pin "B4") (pinfunction "B4_B4") (pintype "bidirectional"))
      (node (ref "USBC_USB") (pin "B9") (pinfunction "B9_B9") (pintype "bidirectional"))
      (node (ref "USBC_VARISTOR") (pin "1") (pinfunction "1_1") (pintype "passive"))
    )
    (net (code "57") (name "unconnected-(BCL_MAX17048G+T10-~{ALERT}-Pad5)") (class "Default")
      (node (ref "BCL_MAX17048G+T10") (pin "5") (pinfunction "~{ALERT}_5") (pintype "output"))
    )
    (net (code "58") (name "unconnected-(EPDH_HEADER-Pad1)") (class "Default")
      (node (ref "EPDH_HEADER") (pin "1") (pinfunction "1_1") (pintype "bidirectional"))
    )
    (net (code "59") (name "unconnected-(EPDH_HEADER-Pad6)") (class "Default")
      (node (ref "EPDH_HEADER") (pin "6") (pinfunction "6_6") (pintype "bidirectional"))
    )
    (net (code "60") (name "unconnected-(EPDH_HEADER-Pad7)") (class "Default")
      (node (ref "EPDH_HEADER") (pin "7") (pinfunction "7_7") (pintype "bidirectional"))
    )
    (net (code "61") (name "unconnected-(ESP32-NC-Pad22)") (class "Default")
      (node (ref "ESP32") (pin "22") (pinfunction "NC_22") (pintype "no_connect"))
    )
    (net (code "62") (name "unconnected-(SDC_SDC-DAT1-PadP8)") (class "Default")
      (node (ref "SDC_SDC") (pin "P8") (pinfunction "DAT1_P8") (pintype "bidirectional"))
    )
    (net (code "63") (name "unconnected-(SDC_SDC-DAT2-PadP1)") (class "Default")
      (node (ref "SDC_SDC") (pin "P1") (pinfunction "DAT2_P1") (pintype "bidirectional"))
    )
    (net (code "64") (name "unconnected-(SDC_SDC-DETECTION_1-PadS1)") (class "Default")
      (node (ref "SDC_SDC") (pin "S1") (pinfunction "DETECTION_1_S1") (pintype "bidirectional"))
    )
    (net (code "65") (name "unconnected-(SDC_SDC-DETECTION_2-PadS2)") (class "Default")
      (node (ref "SDC_SDC") (pin "S2") (pinfunction "DETECTION_2_S2") (pintype "bidirectional"))
    )
    (net (code "66") (name "unconnected-(USBC_USB-PadA8)") (class "Default")
      (node (ref "USBC_USB") (pin "A8") (pinfunction "A8_A8") (pintype "bidirectional"))
    )
    (net (code "67") (name "unconnected-(USBC_USB-PadB8)") (class "Default")
      (node (ref "USBC_USB") (pin "B8") (pinfunction "B8_B8") (pintype "bidirectional"))
    )
    (net (code "68") (name "unconnected-(VOLREG_XC6220A331MR-G-NC-Pad4)") (class "Default")
      (node (ref "VOLREG_XC6220A331MR-G") (pin "4") (pinfunction "NC_4") (pintype "no_connect"))
    )
    (net (code "69") (name "unconnected-(VOLSPV_BD5229G-TR-NC-Pad4)") (class "Default")
      (node (ref "VOLSPV_BD5229G-TR") (pin "4") (pinfunction "NC_4") (pintype "no_connect"))
    )
  )
)
